# DCP23.net
KiCad netlist of a schematic drawn in EAGLE
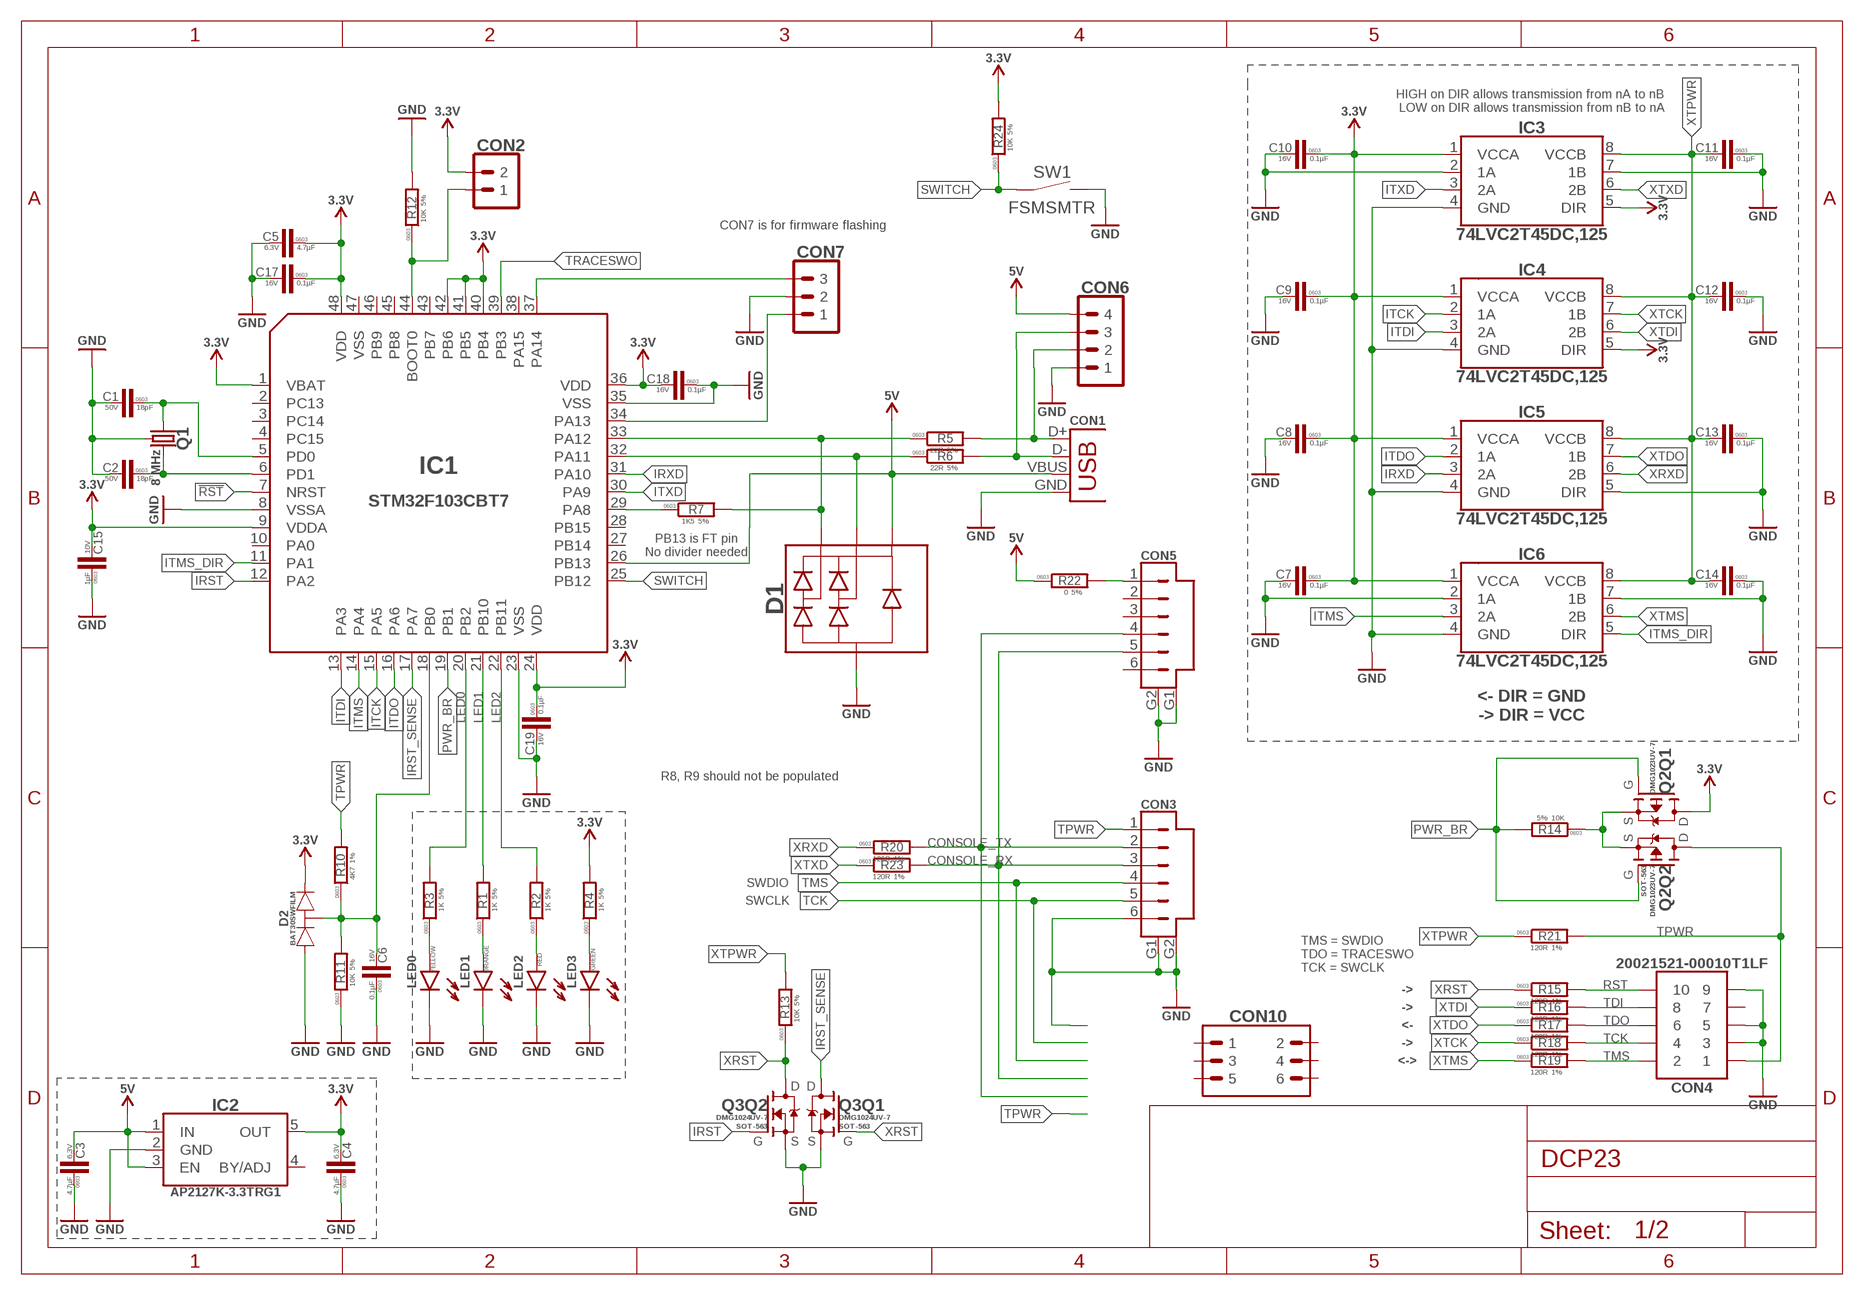
[diagram p0: schematic, sheet 1]

(export (version "E")
  (design (tool "Eeschema 10.0.6"))
  (components
    (comp (ref "C1")
      (value "18pF")
      (footprint "eagle-import:C0603")
      (fields
        (field (name "MANF") "TDK Corporation")
        (field (name "PACKAGE") "0603")
        (field (name "TOLERANCE") "+-5%")
        (field (name "VOLTAGE") "50V")
      )
      (libsource (lib "eagle-import") (part "18PF-0603-50V_5%_NP0"))
    )
    (comp (ref "C2")
      (value "18pF")
      (footprint "eagle-import:C0603")
      (fields
        (field (name "MANF") "TDK Corporation")
        (field (name "PACKAGE") "0603")
        (field (name "TOLERANCE") "+-5%")
        (field (name "VOLTAGE") "50V")
      )
      (libsource (lib "eagle-import") (part "18PF-0603-50V_5%_NP0"))
    )
    (comp (ref "C3")
      (value "4.7µF")
      (footprint "eagle-import:C0603")
      (fields
        (field (name "MANF") "Murata Electronics North America")
        (field (name "PACKAGE") "0603")
        (field (name "TOLERANCE") "+-10%")
        (field (name "VOLTAGE") "6.3V")
      )
      (libsource (lib "eagle-import") (part "4.7µF-0603-6.3V_10%_X5R"))
    )
    (comp (ref "C4")
      (value "4.7µF")
      (footprint "eagle-import:C0603")
      (fields
        (field (name "MANF") "Murata Electronics North America")
        (field (name "PACKAGE") "0603")
        (field (name "TOLERANCE") "+-10%")
        (field (name "VOLTAGE") "6.3V")
      )
      (libsource (lib "eagle-import") (part "4.7µF-0603-6.3V_10%_X5R"))
    )
    (comp (ref "C5")
      (value "4.7µF")
      (footprint "eagle-import:C0603")
      (fields
        (field (name "MANF") "Murata Electronics North America")
        (field (name "PACKAGE") "0603")
        (field (name "TOLERANCE") "+-10%")
        (field (name "VOLTAGE") "6.3V")
      )
      (libsource (lib "eagle-import") (part "4.7µF-0603-6.3V_10%_X5R"))
    )
    (comp (ref "C6")
      (value "0.1µF")
      (footprint "eagle-import:C0603")
      (fields
        (field (name "MANF") "Murata Electronics North America")
        (field (name "PACKAGE") "0603")
        (field (name "TOLERANCE") "+-10%")
        (field (name "VOLTAGE") "16V")
      )
      (libsource (lib "eagle-import") (part "0.1µF-0603-16V_10%_X7R"))
    )
    (comp (ref "C7")
      (value "0.1µF")
      (footprint "eagle-import:C0603")
      (fields
        (field (name "MANF") "Murata Electronics North America")
        (field (name "PACKAGE") "0603")
        (field (name "TOLERANCE") "+-10%")
        (field (name "VOLTAGE") "16V")
      )
      (libsource (lib "eagle-import") (part "0.1µF-0603-16V_10%_X7R"))
    )
    (comp (ref "C8")
      (value "0.1µF")
      (footprint "eagle-import:C0603")
      (fields
        (field (name "MANF") "Murata Electronics North America")
        (field (name "PACKAGE") "0603")
        (field (name "TOLERANCE") "+-10%")
        (field (name "VOLTAGE") "16V")
      )
      (libsource (lib "eagle-import") (part "0.1µF-0603-16V_10%_X7R"))
    )
    (comp (ref "C9")
      (value "0.1µF")
      (footprint "eagle-import:C0603")
      (fields
        (field (name "MANF") "Murata Electronics North America")
        (field (name "PACKAGE") "0603")
        (field (name "TOLERANCE") "+-10%")
        (field (name "VOLTAGE") "16V")
      )
      (libsource (lib "eagle-import") (part "0.1µF-0603-16V_10%_X7R"))
    )
    (comp (ref "C10")
      (value "0.1µF")
      (footprint "eagle-import:C0603")
      (fields
        (field (name "MANF") "Murata Electronics North America")
        (field (name "PACKAGE") "0603")
        (field (name "TOLERANCE") "+-10%")
        (field (name "VOLTAGE") "16V")
      )
      (libsource (lib "eagle-import") (part "0.1µF-0603-16V_10%_X7R"))
    )
    (comp (ref "C11")
      (value "0.1µF")
      (footprint "eagle-import:C0603")
      (fields
        (field (name "MANF") "Murata Electronics North America")
        (field (name "PACKAGE") "0603")
        (field (name "TOLERANCE") "+-10%")
        (field (name "VOLTAGE") "16V")
      )
      (libsource (lib "eagle-import") (part "0.1µF-0603-16V_10%_X7R"))
    )
    (comp (ref "C12")
      (value "0.1µF")
      (footprint "eagle-import:C0603")
      (fields
        (field (name "MANF") "Murata Electronics North America")
        (field (name "PACKAGE") "0603")
        (field (name "TOLERANCE") "+-10%")
        (field (name "VOLTAGE") "16V")
      )
      (libsource (lib "eagle-import") (part "0.1µF-0603-16V_10%_X7R"))
    )
    (comp (ref "C13")
      (value "0.1µF")
      (footprint "eagle-import:C0603")
      (fields
        (field (name "MANF") "Murata Electronics North America")
        (field (name "PACKAGE") "0603")
        (field (name "TOLERANCE") "+-10%")
        (field (name "VOLTAGE") "16V")
      )
      (libsource (lib "eagle-import") (part "0.1µF-0603-16V_10%_X7R"))
    )
    (comp (ref "C14")
      (value "0.1µF")
      (footprint "eagle-import:C0603")
      (fields
        (field (name "MANF") "Murata Electronics North America")
        (field (name "PACKAGE") "0603")
        (field (name "TOLERANCE") "+-10%")
        (field (name "VOLTAGE") "16V")
      )
      (libsource (lib "eagle-import") (part "0.1µF-0603-16V_10%_X7R"))
    )
    (comp (ref "C15")
      (value "1µF")
      (footprint "eagle-import:C0603")
      (fields
        (field (name "MANF") "Murata Electronics North America")
        (field (name "PACKAGE") "0603")
        (field (name "TOLERANCE") "+-10%")
        (field (name "VOLTAGE") "10V")
      )
      (libsource (lib "eagle-import") (part "1µF-0603-10V_10%_X5R"))
    )
    (comp (ref "C17")
      (value "0.1µF")
      (footprint "eagle-import:C0603")
      (fields
        (field (name "MANF") "Murata Electronics North America")
        (field (name "PACKAGE") "0603")
        (field (name "TOLERANCE") "+-10%")
        (field (name "VOLTAGE") "16V")
      )
      (libsource (lib "eagle-import") (part "0.1µF-0603-16V_10%_X7R"))
    )
    (comp (ref "C18")
      (value "0.1µF")
      (footprint "eagle-import:C0603")
      (fields
        (field (name "MANF") "Murata Electronics North America")
        (field (name "PACKAGE") "0603")
        (field (name "TOLERANCE") "+-10%")
        (field (name "VOLTAGE") "16V")
      )
      (libsource (lib "eagle-import") (part "0.1µF-0603-16V_10%_X7R"))
    )
    (comp (ref "C19")
      (value "0.1µF")
      (footprint "eagle-import:C0603")
      (fields
        (field (name "MANF") "Murata Electronics North America")
        (field (name "PACKAGE") "0603")
        (field (name "TOLERANCE") "+-10%")
        (field (name "VOLTAGE") "16V")
      )
      (libsource (lib "eagle-import") (part "0.1µF-0603-16V_10%_X7R"))
    )
    (comp (ref "CON1")
      (value "USB-1")
      (footprint "eagle-import:MICRO_USB_WITH_PEGS")
      (fields (field (name "MANF") "FCI"))
      (libsource (lib "eagle-import") (part "USB-1"))
    )
    (comp (ref "CON2")
      (value "PINHEAD_1X02-2")
      (footprint "eagle-import:1X02-PTH-2")
      (libsource (lib "eagle-import") (part "PINHEAD_1X02-2"))
    )
    (comp (ref "CON3")
      (value "CON-6P-SM06B")
      (footprint "eagle-import:SM06B")
      (fields (field (name "MANF") "JST Sales America Inc"))
      (libsource (lib "eagle-import") (part "CON-6P-SM06B"))
    )
    (comp (ref "CON4")
      (value "CON-2X5P")
      (footprint "eagle-import:200215-00010T1LF")
      (fields (field (name "MANF#") "20021521-00010T1LF") (field (name "MANF") "Amphenol ICC (FCI)"))
      (libsource (lib "eagle-import") (part "CON-2X5P"))
    )
    (comp (ref "CON5")
      (value "CON-6P-DF13")
      (footprint "eagle-import:DF13C-6P-1.25V")
      (fields (field (name "MANF") "Hirose Electric Co Ltd"))
      (libsource (lib "eagle-import") (part "CON-6P-DF13"))
    )
    (comp (ref "CON6")
      (value "PINHEAD_1X04-2.54")
      (footprint "eagle-import:1X04-PTH-2.54")
      (libsource (lib "eagle-import") (part "PINHEAD_1X04-2.54"))
    )
    (comp (ref "CON7")
      (value "PINHEAD_1X03-2.54")
      (footprint "eagle-import:1X03-PTH-2.54")
      (libsource (lib "eagle-import") (part "PINHEAD_1X03-2.54"))
    )
    (comp (ref "CON10")
      (value "PINHEAD_2X03-PTH-2.54")
      (footprint "eagle-import:2X03-PTH-2.54")
      (libsource (lib "eagle-import") (part "PINHEAD_2X03-PTH-2.54"))
    )
    (comp (ref "D1")
      (value "PRTR5V0U2X")
      (footprint "eagle-import:SOT143B")
      (fields (field (name "MANF") "NXP USA Inc"))
      (libsource (lib "eagle-import") (part "PRTR5V0U2X"))
    )
    (comp (ref "D2")
      (value "BAT30SWFILM")
      (footprint "eagle-import:SC70")
      (fields (field (name "MANF#") "BAT30SWFILM") (field (name "MANF") "STMicroelectronics"))
      (libsource (lib "eagle-import") (part "BAT30SWFILM"))
    )
    (comp (ref "IC1")
      (value "STM32F103CBT7")
      (footprint "eagle-import:LQFP48")
      (fields (field (name "MANF#") "STM32F103CBT7") (field (name "MANF") "STMicroelectronics"))
      (libsource (lib "eagle-import") (part "STM32F103CBT7"))
    )
    (comp (ref "IC2")
      (value "AP2127-3.3")
      (footprint "eagle-import:SOT23-5")
      (fields (field (name "MANF") "Diodes Incorporated") (field (name "MANF#") "AP2127K-3.3TRG1"))
      (libsource (lib "eagle-import") (part "AP2127-3.3"))
    )
    (comp (ref "IC3")
      (value "74LVC2T45")
      (footprint "eagle-import:VSSOP8")
      (fields (field (name "MANF#") "74LVC2T45DC,125") (field (name "MANF") "Nexperia USA Inc"))
      (libsource (lib "eagle-import") (part "74LVC2T45"))
    )
    (comp (ref "IC4")
      (value "74LVC2T45")
      (footprint "eagle-import:VSSOP8")
      (fields (field (name "MANF#") "74LVC2T45DC,125") (field (name "MANF") "Nexperia USA Inc"))
      (libsource (lib "eagle-import") (part "74LVC2T45"))
    )
    (comp (ref "IC5")
      (value "74LVC2T45")
      (footprint "eagle-import:VSSOP8")
      (fields (field (name "MANF#") "74LVC2T45DC,125") (field (name "MANF") "Nexperia USA Inc"))
      (libsource (lib "eagle-import") (part "74LVC2T45"))
    )
    (comp (ref "IC6")
      (value "74LVC2T45")
      (footprint "eagle-import:VSSOP8")
      (fields (field (name "MANF#") "74LVC2T45DC,125") (field (name "MANF") "Nexperia USA Inc"))
      (libsource (lib "eagle-import") (part "74LVC2T45"))
    )
    (comp (ref "LED0")
      (value "LED-0603")
      (footprint "eagle-import:LED0603")
      (fields (field (name "COLOR") "YELLOW"))
      (libsource (lib "eagle-import") (part "LED-0603"))
    )
    (comp (ref "LED1")
      (value "LED-0603")
      (footprint "eagle-import:LED0603")
      (fields (field (name "COLOR") "ORANGE"))
      (libsource (lib "eagle-import") (part "LED-0603"))
    )
    (comp (ref "LED2")
      (value "LED-0603")
      (footprint "eagle-import:LED0603")
      (fields (field (name "COLOR") "RED"))
      (libsource (lib "eagle-import") (part "LED-0603"))
    )
    (comp (ref "LED3")
      (value "LED-0603")
      (footprint "eagle-import:LED0603")
      (fields (field (name "COLOR") "GREEN"))
      (libsource (lib "eagle-import") (part "LED-0603"))
    )
    (comp (ref "Q1")
      (value "8 MHz")
      (footprint "eagle-import:OSCILLATOR-5.0X3.2-4P")
      (fields (field (name "MANF") "Abracon LLC"))
      (libsource (lib "eagle-import") (part "CRYSTAL-4P-3.2X5-4P-8MHZ"))
    )
    (comp (ref "Q2")
      (value "DMG1023UV-7")
      (footprint "eagle-import:SOT-563")
      (fields
        (field (name "MANF#") "DMG1023UV-7")
        (field (name "MANF") "Diodes Incorporated")
        (field (name "PACKAGE") "SOT-563")
      )
      (libsource (lib "eagle-import") (part "DMG1023UV-7"))
    )
    (comp (ref "Q3")
      (value "DMG1024UV-7")
      (footprint "eagle-import:SOT-563")
      (fields
        (field (name "MANF#") "DMG1024UV-7")
        (field (name "PACKAGE") "SOT-563")
        (field (name "MANF") "Diodes Incorporated")
      )
      (libsource (lib "eagle-import") (part "DMG1024UV-7"))
    )
    (comp (ref "R1")
      (value "1K")
      (footprint "eagle-import:R0603")
      (fields (field (name "MANF") "Yageo") (field (name "PACKAGE") "0603") (field (name "TOLERANCE") "5%"))
      (libsource (lib "eagle-import") (part "1K-0603-5%"))
    )
    (comp (ref "R2")
      (value "1K")
      (footprint "eagle-import:R0603")
      (fields (field (name "MANF") "Yageo") (field (name "PACKAGE") "0603") (field (name "TOLERANCE") "5%"))
      (libsource (lib "eagle-import") (part "1K-0603-5%"))
    )
    (comp (ref "R3")
      (value "1K")
      (footprint "eagle-import:R0603")
      (fields (field (name "MANF") "Yageo") (field (name "PACKAGE") "0603") (field (name "TOLERANCE") "5%"))
      (libsource (lib "eagle-import") (part "1K-0603-5%"))
    )
    (comp (ref "R4")
      (value "1K")
      (footprint "eagle-import:R0603")
      (fields (field (name "MANF") "Yageo") (field (name "PACKAGE") "0603") (field (name "TOLERANCE") "5%"))
      (libsource (lib "eagle-import") (part "1K-0603-5%"))
    )
    (comp (ref "R5")
      (value "22R")
      (footprint "eagle-import:R0603")
      (fields (field (name "PACKAGE") "0603") (field (name "TOLERANCE") "5%") (field (name "MANF") "Yageo"))
      (libsource (lib "eagle-import") (part "R-0603-5%"))
    )
    (comp (ref "R6")
      (value "22R")
      (footprint "eagle-import:R0603")
      (fields (field (name "PACKAGE") "0603") (field (name "TOLERANCE") "5%") (field (name "MANF") "Yageo"))
      (libsource (lib "eagle-import") (part "R-0603-5%"))
    )
    (comp (ref "R7")
      (value "1K5")
      (footprint "eagle-import:R0603")
      (fields (field (name "PACKAGE") "0603") (field (name "TOLERANCE") "5%") (field (name "MANF") "Yageo"))
      (libsource (lib "eagle-import") (part "R-0603-5%"))
    )
    (comp (ref "R10")
      (value "4K7")
      (footprint "eagle-import:R0603")
      (fields (field (name "MANF") "Yageo") (field (name "PACKAGE") "0603") (field (name "TOLERANCE") "1%"))
      (libsource (lib "eagle-import") (part "4K7-0603-1%"))
    )
    (comp (ref "R11")
      (value "10K")
      (footprint "eagle-import:R0603")
      (fields (field (name "MANF") "Yageo") (field (name "PACKAGE") "0603") (field (name "TOLERANCE") "5%"))
      (libsource (lib "eagle-import") (part "10K-0603-5%"))
    )
    (comp (ref "R12")
      (value "10K")
      (footprint "eagle-import:R0603")
      (fields (field (name "MANF") "Yageo") (field (name "PACKAGE") "0603") (field (name "TOLERANCE") "5%"))
      (libsource (lib "eagle-import") (part "10K-0603-5%"))
    )
    (comp (ref "R13")
      (value "10K")
      (footprint "eagle-import:R0603")
      (fields (field (name "MANF") "Yageo") (field (name "PACKAGE") "0603") (field (name "TOLERANCE") "5%"))
      (libsource (lib "eagle-import") (part "10K-0603-5%"))
    )
    (comp (ref "R14")
      (value "10K")
      (footprint "eagle-import:R0603")
      (fields (field (name "MANF") "Yageo") (field (name "PACKAGE") "0603") (field (name "TOLERANCE") "5%"))
      (libsource (lib "eagle-import") (part "10K-0603-5%"))
    )
    (comp (ref "R15")
      (value "120R")
      (footprint "eagle-import:R0603")
      (fields (field (name "MANF") "Yageo") (field (name "PACKAGE") "0603") (field (name "TOLERANCE") "1%"))
      (libsource (lib "eagle-import") (part "120R-0603-1%"))
    )
    (comp (ref "R16")
      (value "120R")
      (footprint "eagle-import:R0603")
      (fields (field (name "MANF") "Yageo") (field (name "PACKAGE") "0603") (field (name "TOLERANCE") "1%"))
      (libsource (lib "eagle-import") (part "120R-0603-1%"))
    )
    (comp (ref "R17")
      (value "120R")
      (footprint "eagle-import:R0603")
      (fields (field (name "MANF") "Yageo") (field (name "PACKAGE") "0603") (field (name "TOLERANCE") "1%"))
      (libsource (lib "eagle-import") (part "120R-0603-1%"))
    )
    (comp (ref "R18")
      (value "120R")
      (footprint "eagle-import:R0603")
      (fields (field (name "MANF") "Yageo") (field (name "PACKAGE") "0603") (field (name "TOLERANCE") "1%"))
      (libsource (lib "eagle-import") (part "120R-0603-1%"))
    )
    (comp (ref "R19")
      (value "120R")
      (footprint "eagle-import:R0603")
      (fields (field (name "MANF") "Yageo") (field (name "PACKAGE") "0603") (field (name "TOLERANCE") "1%"))
      (libsource (lib "eagle-import") (part "120R-0603-1%"))
    )
    (comp (ref "R20")
      (value "120R")
      (footprint "eagle-import:R0603")
      (fields (field (name "MANF") "Yageo") (field (name "PACKAGE") "0603") (field (name "TOLERANCE") "1%"))
      (libsource (lib "eagle-import") (part "120R-0603-1%"))
    )
    (comp (ref "R21")
      (value "120R")
      (footprint "eagle-import:R0603")
      (fields (field (name "MANF") "Yageo") (field (name "PACKAGE") "0603") (field (name "TOLERANCE") "1%"))
      (libsource (lib "eagle-import") (part "120R-0603-1%"))
    )
    (comp (ref "R22")
      (value "0")
      (footprint "eagle-import:R0603")
      (fields (field (name "MANF") "Yageo") (field (name "PACKAGE") "0603") (field (name "TOLERANCE") "5%"))
      (libsource (lib "eagle-import") (part "0R-0603-5%"))
    )
    (comp (ref "R23")
      (value "120R")
      (footprint "eagle-import:R0603")
      (fields (field (name "MANF") "Yageo") (field (name "PACKAGE") "0603") (field (name "TOLERANCE") "1%"))
      (libsource (lib "eagle-import") (part "120R-0603-1%"))
    )
    (comp (ref "R24")
      (value "10K")
      (footprint "eagle-import:R0603")
      (fields (field (name "MANF") "Yageo") (field (name "PACKAGE") "0603") (field (name "TOLERANCE") "5%"))
      (libsource (lib "eagle-import") (part "10K-0603-5%"))
    )
    (comp (ref "SW1")
      (value "TACT_SWITCH-FSMSM")
      (footprint "eagle-import:FSMSM")
      (fields (field (name "MANF") "TE Connectivity ALCOSWITCH Switches"))
      (libsource (lib "eagle-import") (part "TACT_SWITCH-FSMSM"))
    )
  )
  (nets
    (net (code "1") (name "CONSOLE_RX") (class "Default")
      (node (ref "CON3") (pin "3") (pinfunction "3_3") (pintype "passive"))
      (node (ref "CON5") (pin "5") (pinfunction "5_5") (pintype "passive"))
      (node (ref "R23") (pin "P$2") (pinfunction "2_P$2") (pintype "passive"))
    )
    (net (code "2") (name "CONSOLE_TX") (class "Default")
      (node (ref "CON3") (pin "2") (pinfunction "2_2") (pintype "passive"))
      (node (ref "CON5") (pin "4") (pinfunction "4_4") (pintype "passive"))
      (node (ref "R20") (pin "P$2") (pinfunction "2_P$2") (pintype "passive"))
    )
    (net (code "3") (name "GND") (class "Default")
      (node (ref "C1") (pin "P$2") (pinfunction "2_P$2") (pintype "passive"))
      (node (ref "C10") (pin "P$2") (pinfunction "2_P$2") (pintype "passive"))
      (node (ref "C11") (pin "P$1") (pinfunction "1_P$1") (pintype "passive"))
      (node (ref "C12") (pin "P$1") (pinfunction "1_P$1") (pintype "passive"))
      (node (ref "C13") (pin "P$1") (pinfunction "1_P$1") (pintype "passive"))
      (node (ref "C14") (pin "P$1") (pinfunction "1_P$1") (pintype "passive"))
      (node (ref "C15") (pin "P$1") (pinfunction "1_P$1") (pintype "passive"))
      (node (ref "C17") (pin "P$2") (pinfunction "2_P$2") (pintype "passive"))
      (node (ref "C18") (pin "P$1") (pinfunction "1_P$1") (pintype "passive"))
      (node (ref "C19") (pin "P$2") (pinfunction "2_P$2") (pintype "passive"))
      (node (ref "C2") (pin "P$2") (pinfunction "2_P$2") (pintype "passive"))
      (node (ref "C3") (pin "P$1") (pinfunction "1_P$1") (pintype "passive"))
      (node (ref "C4") (pin "P$1") (pinfunction "1_P$1") (pintype "passive"))
      (node (ref "C5") (pin "P$2") (pinfunction "2_P$2") (pintype "passive"))
      (node (ref "C6") (pin "P$1") (pinfunction "1_P$1") (pintype "passive"))
      (node (ref "C7") (pin "P$2") (pinfunction "2_P$2") (pintype "passive"))
      (node (ref "C8") (pin "P$2") (pinfunction "2_P$2") (pintype "passive"))
      (node (ref "C9") (pin "P$2") (pinfunction "2_P$2") (pintype "passive"))
      (node (ref "CON1") (pin "GND") (pinfunction "GND_GND") (pintype "bidirectional"))
      (node (ref "CON3") (pin "6") (pinfunction "6_6") (pintype "passive"))
      (node (ref "CON3") (pin "G1") (pinfunction "G1_G1") (pintype "passive"))
      (node (ref "CON3") (pin "G2") (pinfunction "G2_G2") (pintype "passive"))
      (node (ref "CON4") (pin "3") (pinfunction "3_3") (pintype "bidirectional"))
      (node (ref "CON4") (pin "5") (pinfunction "5_5") (pintype "bidirectional"))
      (node (ref "CON4") (pin "9") (pinfunction "9_9") (pintype "bidirectional"))
      (node (ref "CON5") (pin "G1") (pinfunction "G2_G1") (pintype "passive"))
      (node (ref "CON5") (pin "G2") (pinfunction "G1_G2") (pintype "passive"))
      (node (ref "CON6") (pin "1") (pinfunction "1_1") (pintype "passive"))
      (node (ref "CON7") (pin "2") (pinfunction "2_2") (pintype "passive"))
      (node (ref "D1") (pin "1") (pinfunction "C_1") (pintype "bidirectional"))
      (node (ref "D2") (pin "1") (pinfunction "A_1") (pintype "passive"))
      (node (ref "IC1") (pin "23") (pinfunction "VSS_23") (pintype "bidirectional"))
      (node (ref "IC1") (pin "35") (pinfunction "VSS_35") (pintype "bidirectional"))
      (node (ref "IC1") (pin "8") (pinfunction "VSSA_8") (pintype "bidirectional"))
      (node (ref "IC2") (pin "2") (pinfunction "GND_2") (pintype "power_in"))
      (node (ref "IC3") (pin "2") (pinfunction "1A_2") (pintype "bidirectional"))
      (node (ref "IC3") (pin "4") (pinfunction "GND_4") (pintype "bidirectional"))
      (node (ref "IC3") (pin "7") (pinfunction "1B_7") (pintype "bidirectional"))
      (node (ref "IC4") (pin "4") (pinfunction "GND_4") (pintype "bidirectional"))
      (node (ref "IC5") (pin "4") (pinfunction "GND_4") (pintype "bidirectional"))
      (node (ref "IC5") (pin "5") (pinfunction "DIR_5") (pintype "bidirectional"))
      (node (ref "IC6") (pin "2") (pinfunction "1A_2") (pintype "bidirectional"))
      (node (ref "IC6") (pin "4") (pinfunction "GND_4") (pintype "bidirectional"))
      (node (ref "IC6") (pin "7") (pinfunction "1B_7") (pintype "bidirectional"))
      (node (ref "LED0") (pin "C") (pinfunction "C_C") (pintype "bidirectional"))
      (node (ref "LED1") (pin "C") (pinfunction "C_C") (pintype "bidirectional"))
      (node (ref "LED2") (pin "C") (pinfunction "C_C") (pintype "bidirectional"))
      (node (ref "LED3") (pin "C") (pinfunction "C_C") (pintype "bidirectional"))
      (node (ref "Q1") (pin "2") (pinfunction "GND_2") (pintype "bidirectional"))
      (node (ref "Q1") (pin "4") (pinfunction "GND_4") (pintype "bidirectional"))
      (node (ref "Q3") (pin "1") (pinfunction "S_1") (pintype "passive"))
      (node (ref "Q3") (pin "4") (pinfunction "S_4") (pintype "passive"))
      (node (ref "R11") (pin "P$1") (pinfunction "1_P$1") (pintype "passive"))
      (node (ref "R12") (pin "P$2") (pinfunction "2_P$2") (pintype "passive"))
      (node (ref "SW1") (pin "P$2") (pinfunction "2_P$2") (pintype "bidirectional"))
    )
    (net (code "4") (name "IRST") (class "Default")
      (node (ref "IC1") (pin "12") (pinfunction "PA2_12") (pintype "bidirectional"))
      (node (ref "Q3") (pin "5") (pinfunction "G_5") (pintype "passive"))
    )
    (net (code "5") (name "IRST_SENSE") (class "Default")
      (node (ref "IC1") (pin "17") (pinfunction "PA7_17") (pintype "bidirectional"))
      (node (ref "Q3") (pin "6") (pinfunction "D_6") (pintype "passive"))
    )
    (net (code "6") (name "IRXD") (class "Default")
      (node (ref "IC1") (pin "31") (pinfunction "PA10_31") (pintype "bidirectional"))
      (node (ref "IC5") (pin "3") (pinfunction "2A_3") (pintype "bidirectional"))
    )
    (net (code "7") (name "ITCK") (class "Default")
      (node (ref "IC1") (pin "15") (pinfunction "PA5_15") (pintype "bidirectional"))
      (node (ref "IC4") (pin "2") (pinfunction "1A_2") (pintype "bidirectional"))
    )
    (net (code "8") (name "ITDI") (class "Default")
      (node (ref "IC1") (pin "13") (pinfunction "PA3_13") (pintype "bidirectional"))
      (node (ref "IC4") (pin "3") (pinfunction "2A_3") (pintype "bidirectional"))
    )
    (net (code "9") (name "ITDO") (class "Default")
      (node (ref "IC1") (pin "16") (pinfunction "PA6_16") (pintype "bidirectional"))
      (node (ref "IC5") (pin "2") (pinfunction "1A_2") (pintype "bidirectional"))
    )
    (net (code "10") (name "ITMS") (class "Default")
      (node (ref "IC1") (pin "14") (pinfunction "PA4_14") (pintype "bidirectional"))
      (node (ref "IC6") (pin "3") (pinfunction "2A_3") (pintype "bidirectional"))
    )
    (net (code "11") (name "ITMS_DIR") (class "Default")
      (node (ref "IC1") (pin "11") (pinfunction "PA1_11") (pintype "bidirectional"))
      (node (ref "IC6") (pin "5") (pinfunction "DIR_5") (pintype "bidirectional"))
    )
    (net (code "12") (name "ITXD") (class "Default")
      (node (ref "IC1") (pin "30") (pinfunction "PA9_30") (pintype "bidirectional"))
      (node (ref "IC3") (pin "3") (pinfunction "2A_3") (pintype "bidirectional"))
    )
    (net (code "13") (name "LED0") (class "Default")
      (node (ref "IC1") (pin "20") (pinfunction "PB2_20") (pintype "bidirectional"))
      (node (ref "R3") (pin "P$2") (pinfunction "2_P$2") (pintype "passive"))
    )
    (net (code "14") (name "LED1") (class "Default")
      (node (ref "IC1") (pin "21") (pinfunction "PB10_21") (pintype "bidirectional"))
      (node (ref "R1") (pin "P$2") (pinfunction "2_P$2") (pintype "passive"))
    )
    (net (code "15") (name "LED2") (class "Default")
      (node (ref "IC1") (pin "22") (pinfunction "PB11_22") (pintype "bidirectional"))
      (node (ref "R2") (pin "P$2") (pinfunction "2_P$2") (pintype "passive"))
    )
    (net (code "16") (name "Net-(C1-1)") (class "Default")
      (node (ref "C1") (pin "P$1") (pinfunction "1_P$1") (pintype "passive"))
      (node (ref "IC1") (pin "5") (pinfunction "PD0_5") (pintype "bidirectional"))
      (node (ref "Q1") (pin "1") (pinfunction "1_1") (pintype "passive"))
    )
    (net (code "17") (name "Net-(C2-1)") (class "Default")
      (node (ref "C2") (pin "P$1") (pinfunction "1_P$1") (pintype "passive"))
      (node (ref "IC1") (pin "6") (pinfunction "PD1_6") (pintype "bidirectional"))
      (node (ref "Q1") (pin "3") (pinfunction "2_3") (pintype "passive"))
    )
    (net (code "18") (name "Net-(C6-2)") (class "Default")
      (node (ref "C6") (pin "P$2") (pinfunction "2_P$2") (pintype "passive"))
      (node (ref "D2") (pin "3") (pinfunction "COMMON_3") (pintype "bidirectional"))
      (node (ref "IC1") (pin "18") (pinfunction "PB0_18") (pintype "bidirectional"))
      (node (ref "R10") (pin "P$1") (pinfunction "1_P$1") (pintype "passive"))
      (node (ref "R11") (pin "P$2") (pinfunction "2_P$2") (pintype "passive"))
    )
    (net (code "19") (name "Net-(CON1-PadD+)") (class "Default")
      (node (ref "CON1") (pin "D+") (pinfunction "D+_D+") (pintype "bidirectional"))
      (node (ref "CON6") (pin "2") (pinfunction "2_2") (pintype "passive"))
      (node (ref "R5") (pin "2") (pinfunction "2_2") (pintype "passive"))
    )
    (net (code "20") (name "Net-(CON1-PadD-)") (class "Default")
      (node (ref "CON1") (pin "D-") (pinfunction "D-_D-") (pintype "bidirectional"))
      (node (ref "CON6") (pin "3") (pinfunction "3_3") (pintype "passive"))
      (node (ref "R6") (pin "2") (pinfunction "2_2") (pintype "passive"))
    )
    (net (code "21") (name "Net-(D1-D1)") (class "Default")
      (node (ref "D1") (pin "2") (pinfunction "D1_2") (pintype "bidirectional"))
      (node (ref "IC1") (pin "33") (pinfunction "PA12_33") (pintype "bidirectional"))
      (node (ref "R5") (pin "1") (pinfunction "1_1") (pintype "passive"))
      (node (ref "R7") (pin "2") (pinfunction "2_2") (pintype "passive"))
    )
    (net (code "22") (name "Net-(D1-D2)") (class "Default")
      (node (ref "D1") (pin "3") (pinfunction "D2_3") (pintype "bidirectional"))
      (node (ref "IC1") (pin "32") (pinfunction "PA11_32") (pintype "bidirectional"))
      (node (ref "R6") (pin "1") (pinfunction "1_1") (pintype "passive"))
    )
    (net (code "23") (name "Net-(IC1-BOOT0)") (class "Default")
      (node (ref "CON2") (pin "1") (pinfunction "1_1") (pintype "passive"))
      (node (ref "IC1") (pin "44") (pinfunction "BOOT0_44") (pintype "bidirectional"))
      (node (ref "R12") (pin "P$1") (pinfunction "1_P$1") (pintype "passive"))
    )
    (net (code "24") (name "Net-(IC1-PA8)") (class "Default")
      (node (ref "IC1") (pin "29") (pinfunction "PA8_29") (pintype "bidirectional"))
      (node (ref "R7") (pin "1") (pinfunction "1_1") (pintype "passive"))
    )
    (net (code "25") (name "Net-(IC1-PA13)") (class "Default")
      (node (ref "CON7") (pin "1") (pinfunction "1_1") (pintype "passive"))
      (node (ref "IC1") (pin "34") (pinfunction "PA13_34") (pintype "bidirectional"))
    )
    (net (code "26") (name "Net-(IC1-PA14)") (class "Default")
      (node (ref "CON7") (pin "3") (pinfunction "3_3") (pintype "passive"))
      (node (ref "IC1") (pin "37") (pinfunction "PA14_37") (pintype "bidirectional"))
    )
    (net (code "27") (name "Net-(Q2A-S)") (class "Default")
      (node (ref "Q2") (pin "1") (pinfunction "S_1") (pintype "passive"))
      (node (ref "Q2") (pin "4") (pinfunction "S_4") (pintype "passive"))
      (node (ref "R14") (pin "P$1") (pinfunction "1_P$1") (pintype "passive"))
    )
    (net (code "28") (name "Net-(R1-1)") (class "Default")
      (node (ref "LED1") (pin "A") (pinfunction "A_A") (pintype "bidirectional"))
      (node (ref "R1") (pin "P$1") (pinfunction "1_P$1") (pintype "passive"))
    )
    (net (code "29") (name "Net-(R2-1)") (class "Default")
      (node (ref "LED2") (pin "A") (pinfunction "A_A") (pintype "bidirectional"))
      (node (ref "R2") (pin "P$1") (pinfunction "1_P$1") (pintype "passive"))
    )
    (net (code "30") (name "Net-(R3-1)") (class "Default")
      (node (ref "LED0") (pin "A") (pinfunction "A_A") (pintype "bidirectional"))
      (node (ref "R3") (pin "P$1") (pinfunction "1_P$1") (pintype "passive"))
    )
    (net (code "31") (name "Net-(R4-1)") (class "Default")
      (node (ref "LED3") (pin "A") (pinfunction "A_A") (pintype "bidirectional"))
      (node (ref "R4") (pin "P$1") (pinfunction "1_P$1") (pintype "passive"))
    )
    (net (code "32") (name "Net-(R22-2)") (class "Default")
      (node (ref "CON5") (pin "1") (pinfunction "1_1") (pintype "passive"))
      (node (ref "R22") (pin "P$2") (pinfunction "2_P$2") (pintype "passive"))
    )
    (net (code "33") (name "PWR_BR") (class "Default")
      (node (ref "IC1") (pin "19") (pinfunction "PB1_19") (pintype "bidirectional"))
      (node (ref "Q2") (pin "2") (pinfunction "G_2") (pintype "passive"))
      (node (ref "Q2") (pin "5") (pinfunction "G_5") (pintype "passive"))
      (node (ref "R14") (pin "P$2") (pinfunction "2_P$2") (pintype "passive"))
    )
    (net (code "34") (name "RST") (class "Default")
      (node (ref "CON4") (pin "10") (pinfunction "10_10") (pintype "bidirectional"))
      (node (ref "R15") (pin "P$2") (pinfunction "2_P$2") (pintype "passive"))
    )
    (net (code "35") (name "SWITCH") (class "Default")
      (node (ref "IC1") (pin "25") (pinfunction "PB12_25") (pintype "bidirectional"))
      (node (ref "R24") (pin "P$1") (pinfunction "1_P$1") (pintype "passive"))
      (node (ref "SW1") (pin "P$1") (pinfunction "1_P$1") (pintype "bidirectional"))
    )
    (net (code "36") (name "TCK") (class "Default")
      (node (ref "CON3") (pin "5") (pinfunction "5_5") (pintype "passive"))
      (node (ref "CON4") (pin "4") (pinfunction "4_4") (pintype "bidirectional"))
      (node (ref "R18") (pin "P$2") (pinfunction "2_P$2") (pintype "passive"))
    )
    (net (code "37") (name "TDI") (class "Default")
      (node (ref "CON4") (pin "8") (pinfunction "8_8") (pintype "bidirectional"))
      (node (ref "R16") (pin "P$2") (pinfunction "2_P$2") (pintype "passive"))
    )
    (net (code "38") (name "TDO") (class "Default")
      (node (ref "CON4") (pin "6") (pinfunction "6_6") (pintype "bidirectional"))
      (node (ref "R17") (pin "P$2") (pinfunction "2_P$2") (pintype "passive"))
    )
    (net (code "39") (name "TMS") (class "Default")
      (node (ref "CON3") (pin "4") (pinfunction "4_4") (pintype "passive"))
      (node (ref "CON4") (pin "2") (pinfunction "2_2") (pintype "bidirectional"))
      (node (ref "R19") (pin "P$2") (pinfunction "2_P$2") (pintype "passive"))
    )
    (net (code "40") (name "TPWR") (class "Default")
      (node (ref "CON3") (pin "1") (pinfunction "1_1") (pintype "passive"))
      (node (ref "CON4") (pin "1") (pinfunction "1_1") (pintype "bidirectional"))
      (node (ref "Q2") (pin "6") (pinfunction "D_6") (pintype "passive"))
      (node (ref "R10") (pin "P$2") (pinfunction "2_P$2") (pintype "passive"))
      (node (ref "R21") (pin "P$2") (pinfunction "2_P$2") (pintype "passive"))
    )
    (net (code "41") (name "TRACESWO") (class "Default")
      (node (ref "IC1") (pin "39") (pinfunction "PB3_39") (pintype "bidirectional"))
    )
    (net (code "42") (name "VDD_3V3") (class "Default")
      (node (ref "C10") (pin "P$1") (pinfunction "1_P$1") (pintype "passive"))
      (node (ref "C15") (pin "P$2") (pinfunction "2_P$2") (pintype "passive"))
      (node (ref "C17") (pin "P$1") (pinfunction "1_P$1") (pintype "passive"))
      (node (ref "C18") (pin "P$2") (pinfunction "2_P$2") (pintype "passive"))
      (node (ref "C19") (pin "P$1") (pinfunction "1_P$1") (pintype "passive"))
      (node (ref "C4") (pin "P$2") (pinfunction "2_P$2") (pintype "passive"))
      (node (ref "C5") (pin "P$1") (pinfunction "1_P$1") (pintype "passive"))
      (node (ref "C7") (pin "P$1") (pinfunction "1_P$1") (pintype "passive"))
      (node (ref "C8") (pin "P$1") (pinfunction "1_P$1") (pintype "passive"))
      (node (ref "C9") (pin "P$1") (pinfunction "1_P$1") (pintype "passive"))
      (node (ref "CON2") (pin "2") (pinfunction "2_2") (pintype "passive"))
      (node (ref "D2") (pin "2") (pinfunction "C_2") (pintype "passive"))
      (node (ref "IC1") (pin "1") (pinfunction "VBAT_1") (pintype "bidirectional"))
      (node (ref "IC1") (pin "24") (pinfunction "VDD_24") (pintype "bidirectional"))
      (node (ref "IC1") (pin "36") (pinfunction "VDD_36") (pintype "bidirectional"))
      (node (ref "IC1") (pin "40") (pinfunction "PB4_40") (pintype "bidirectional"))
      (node (ref "IC1") (pin "41") (pinfunction "PB5_41") (pintype "bidirectional"))
      (node (ref "IC1") (pin "42") (pinfunction "PB6_42") (pintype "bidirectional"))
      (node (ref "IC1") (pin "48") (pinfunction "VDD_48") (pintype "bidirectional"))
      (node (ref "IC1") (pin "9") (pinfunction "VDDA_9") (pintype "bidirectional"))
      (node (ref "IC2") (pin "5") (pinfunction "OUT_5") (pintype "power_in"))
      (node (ref "IC3") (pin "1") (pinfunction "VCCA_1") (pintype "bidirectional"))
      (node (ref "IC3") (pin "5") (pinfunction "DIR_5") (pintype "bidirectional"))
      (node (ref "IC4") (pin "1") (pinfunction "VCCA_1") (pintype "bidirectional"))
      (node (ref "IC4") (pin "5") (pinfunction "DIR_5") (pintype "bidirectional"))
      (node (ref "IC5") (pin "1") (pinfunction "VCCA_1") (pintype "bidirectional"))
      (node (ref "IC6") (pin "1") (pinfunction "VCCA_1") (pintype "bidirectional"))
      (node (ref "Q2") (pin "3") (pinfunction "D_3") (pintype "passive"))
      (node (ref "R24") (pin "P$2") (pinfunction "2_P$2") (pintype "passive"))
      (node (ref "R4") (pin "P$2") (pinfunction "2_P$2") (pintype "passive"))
    )
    (net (code "43") (name "VDD_5V") (class "Default")
      (node (ref "C3") (pin "P$2") (pinfunction "2_P$2") (pintype "passive"))
      (node (ref "CON1") (pin "VBUS") (pinfunction "VBUS_VBUS") (pintype "bidirectional"))
      (node (ref "CON6") (pin "4") (pinfunction "4_4") (pintype "passive"))
      (node (ref "D1") (pin "4") (pinfunction "A_4") (pintype "bidirectional"))
      (node (ref "IC1") (pin "26") (pinfunction "PB13_26") (pintype "bidirectional"))
      (node (ref "IC2") (pin "1") (pinfunction "IN_1") (pintype "power_in"))
      (node (ref "IC2") (pin "3") (pinfunction "EN_3") (pintype "input"))
      (node (ref "R22") (pin "P$1") (pinfunction "1_P$1") (pintype "passive"))
    )
    (net (code "44") (name "XRST") (class "Default")
      (node (ref "Q3") (pin "2") (pinfunction "G_2") (pintype "passive"))
      (node (ref "Q3") (pin "3") (pinfunction "D_3") (pintype "passive"))
      (node (ref "R13") (pin "P$1") (pinfunction "1_P$1") (pintype "passive"))
      (node (ref "R15") (pin "P$1") (pinfunction "1_P$1") (pintype "passive"))
    )
    (net (code "45") (name "XRXD") (class "Default")
      (node (ref "IC5") (pin "6") (pinfunction "2B_6") (pintype "bidirectional"))
      (node (ref "R20") (pin "P$1") (pinfunction "1_P$1") (pintype "passive"))
    )
    (net (code "46") (name "XTCK") (class "Default")
      (node (ref "IC4") (pin "7") (pinfunction "1B_7") (pintype "bidirectional"))
      (node (ref "R18") (pin "P$1") (pinfunction "1_P$1") (pintype "passive"))
    )
    (net (code "47") (name "XTDI") (class "Default")
      (node (ref "IC4") (pin "6") (pinfunction "2B_6") (pintype "bidirectional"))
      (node (ref "R16") (pin "P$1") (pinfunction "1_P$1") (pintype "passive"))
    )
    (net (code "48") (name "XTDO") (class "Default")
      (node (ref "IC5") (pin "7") (pinfunction "1B_7") (pintype "bidirectional"))
      (node (ref "R17") (pin "P$1") (pinfunction "1_P$1") (pintype "passive"))
    )
    (net (code "49") (name "XTMS") (class "Default")
      (node (ref "IC6") (pin "6") (pinfunction "2B_6") (pintype "bidirectional"))
      (node (ref "R19") (pin "P$1") (pinfunction "1_P$1") (pintype "passive"))
    )
    (net (code "50") (name "XTPWR") (class "Default")
      (node (ref "C11") (pin "P$2") (pinfunction "2_P$2") (pintype "passive"))
      (node (ref "C12") (pin "P$2") (pinfunction "2_P$2") (pintype "passive"))
      (node (ref "C13") (pin "P$2") (pinfunction "2_P$2") (pintype "passive"))
      (node (ref "C14") (pin "P$2") (pinfunction "2_P$2") (pintype "passive"))
      (node (ref "IC3") (pin "8") (pinfunction "VCCB_8") (pintype "bidirectional"))
      (node (ref "IC4") (pin "8") (pinfunction "VCCB_8") (pintype "bidirectional"))
      (node (ref "IC5") (pin "8") (pinfunction "VCCB_8") (pintype "bidirectional"))
      (node (ref "IC6") (pin "8") (pinfunction "VCCB_8") (pintype "bidirectional"))
      (node (ref "R13") (pin "P$2") (pinfunction "2_P$2") (pintype "passive"))
      (node (ref "R21") (pin "P$1") (pinfunction "1_P$1") (pintype "passive"))
    )
    (net (code "51") (name "XTXD") (class "Default")
      (node (ref "IC3") (pin "6") (pinfunction "2B_6") (pintype "bidirectional"))
      (node (ref "R23") (pin "P$1") (pinfunction "1_P$1") (pintype "passive"))
    )
    (net (code "52") (name "unconnected-(CON4-Pad7)") (class "Default")
      (node (ref "CON4") (pin "7") (pinfunction "7_7") (pintype "bidirectional"))
    )
    (net (code "53") (name "unconnected-(CON5-Pad2)") (class "Default")
      (node (ref "CON5") (pin "2") (pinfunction "2_2") (pintype "passive"))
    )
    (net (code "54") (name "unconnected-(CON5-Pad3)") (class "Default")
      (node (ref "CON5") (pin "3") (pinfunction "3_3") (pintype "passive"))
    )
    (net (code "55") (name "unconnected-(CON5-Pad6)") (class "Default")
      (node (ref "CON5") (pin "6") (pinfunction "6_6") (pintype "passive"))
    )
    (net (code "56") (name "unconnected-(CON10-Pad1)") (class "Default")
      (node (ref "CON10") (pin "1") (pinfunction "1_1") (pintype "passive"))
    )
    (net (code "57") (name "unconnected-(CON10-Pad2)") (class "Default")
      (node (ref "CON10") (pin "2") (pinfunction "2_2") (pintype "passive"))
    )
    (net (code "58") (name "unconnected-(CON10-Pad3)") (class "Default")
      (node (ref "CON10") (pin "3") (pinfunction "3_3") (pintype "passive"))
    )
    (net (code "59") (name "unconnected-(CON10-Pad4)") (class "Default")
      (node (ref "CON10") (pin "4") (pinfunction "4_4") (pintype "passive"))
    )
    (net (code "60") (name "unconnected-(CON10-Pad5)") (class "Default")
      (node (ref "CON10") (pin "5") (pinfunction "5_5") (pintype "passive"))
    )
    (net (code "61") (name "unconnected-(CON10-Pad6)") (class "Default")
      (node (ref "CON10") (pin "6") (pinfunction "6_6") (pintype "passive"))
    )
    (net (code "62") (name "unconnected-(IC1-PA0-Pad10)") (class "Default")
      (node (ref "IC1") (pin "10") (pinfunction "PA0_10") (pintype "bidirectional"))
    )
    (net (code "63") (name "unconnected-(IC1-PA15-Pad38)") (class "Default")
      (node (ref "IC1") (pin "38") (pinfunction "PA15_38") (pintype "bidirectional"))
    )
    (net (code "64") (name "unconnected-(IC1-PB7-Pad43)") (class "Default")
      (node (ref "IC1") (pin "43") (pinfunction "PB7_43") (pintype "bidirectional"))
    )
    (net (code "65") (name "unconnected-(IC1-PB8-Pad45)") (class "Default")
      (node (ref "IC1") (pin "45") (pinfunction "PB8_45") (pintype "bidirectional"))
    )
    (net (code "66") (name "unconnected-(IC1-PB9-Pad46)") (class "Default")
      (node (ref "IC1") (pin "46") (pinfunction "PB9_46") (pintype "bidirectional"))
    )
    (net (code "67") (name "unconnected-(IC1-PB14-Pad27)") (class "Default")
      (node (ref "IC1") (pin "27") (pinfunction "PB14_27") (pintype "bidirectional"))
    )
    (net (code "68") (name "unconnected-(IC1-PB15-Pad28)") (class "Default")
      (node (ref "IC1") (pin "28") (pinfunction "PB15_28") (pintype "bidirectional"))
    )
    (net (code "69") (name "unconnected-(IC1-PC13-Pad2)") (class "Default")
      (node (ref "IC1") (pin "2") (pinfunction "PC13_2") (pintype "bidirectional"))
    )
    (net (code "70") (name "unconnected-(IC1-PC14-Pad3)") (class "Default")
      (node (ref "IC1") (pin "3") (pinfunction "PC14_3") (pintype "bidirectional"))
    )
    (net (code "71") (name "unconnected-(IC1-PC15-Pad4)") (class "Default")
      (node (ref "IC1") (pin "4") (pinfunction "PC15_4") (pintype "bidirectional"))
    )
    (net (code "72") (name "unconnected-(IC1-VSS-Pad47)") (class "Default")
      (node (ref "IC1") (pin "47") (pinfunction "VSS_47") (pintype "bidirectional"))
    )
    (net (code "73") (name "unconnected-(IC2-BY{slash}ADJ-Pad4)") (class "Default")
      (node (ref "IC2") (pin "4") (pinfunction "BY/ADJ_4") (pintype "bidirectional"))
    )
    (net (code "74") (name "~{RST}") (class "Default")
      (node (ref "IC1") (pin "7") (pinfunction "NRST_7") (pintype "bidirectional"))
    )
  )
)
